# loc_board1.net
KiCad netlist of a schematic drawn in EAGLE
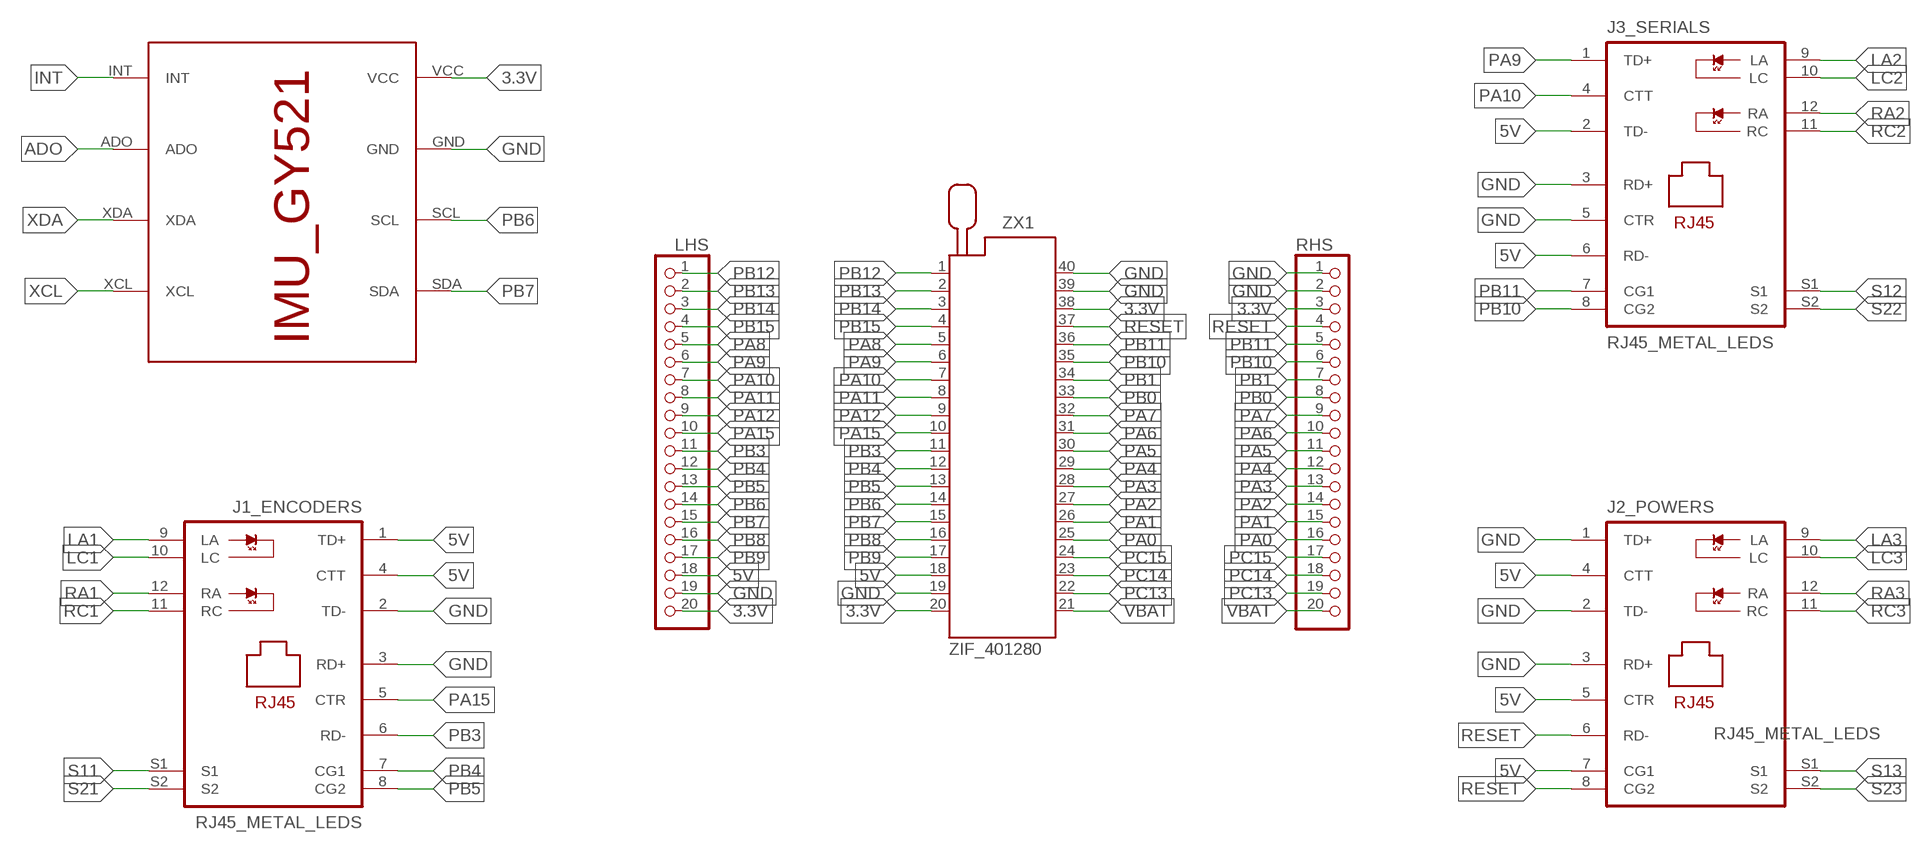
[diagram p0: schematic, sheet 1]

(export (version "E")
  (design (tool "Eeschema 10.0.6"))
  (components
    (comp (ref "IMU_")
      (value "IMU_ROBOCON_GY521")
      (footprint "eagle-import:IMU_GY521")
      (libsource (lib "eagle-import") (part "IMU_ROBOCON_GY521"))
    )
    (comp (ref "J1_ENCODERS")
      (value "RJ45_METAL_LEDS")
      (footprint "eagle-import:J0-A_B_F")
      (libsource (lib "eagle-import") (part "RJ45_METAL_LEDS"))
    )
    (comp (ref "J2_POWERS")
      (value "RJ45_METAL_LEDS")
      (footprint "eagle-import:J0-A_B_F")
      (libsource (lib "eagle-import") (part "RJ45_METAL_LEDS"))
    )
    (comp (ref "J3_SERIALS")
      (value "RJ45_METAL_LEDS")
      (footprint "eagle-import:J0-A_B_F")
      (libsource (lib "eagle-import") (part "RJ45_METAL_LEDS"))
    )
    (comp (ref "LHS")
      (value "PINHD-1X20")
      (footprint "eagle-import:1X20")
      (libsource (lib "eagle-import") (part "PINHD-1X20"))
    )
    (comp (ref "RHS")
      (value "PINHD-1X20")
      (footprint "eagle-import:1X20")
      (libsource (lib "eagle-import") (part "PINHD-1X20"))
    )
    (comp (ref "ZX1")
      (value "ZIF_401280")
      (footprint "eagle-import:240-1280-00-0602J")
      (libsource (lib "eagle-import") (part "ZIF_401280"))
    )
  )
  (nets
    (net (code "1") (name "3.3V") (class "Default")
      (node (ref "IMU_") (pin "VCC") (pinfunction "VCC_VCC") (pintype "bidirectional"))
      (node (ref "LHS") (pin "20") (pinfunction "20_20") (pintype "passive"))
      (node (ref "RHS") (pin "3") (pinfunction "3_3") (pintype "passive"))
      (node (ref "ZX1") (pin "20") (pinfunction "20_20") (pintype "passive"))
      (node (ref "ZX1") (pin "38") (pinfunction "38_38") (pintype "passive"))
    )
    (net (code "2") (name "5V") (class "Default")
      (node (ref "J1_ENCODERS") (pin "1") (pinfunction "TD+_1") (pintype "passive"))
      (node (ref "J1_ENCODERS") (pin "4") (pinfunction "CTT_4") (pintype "passive"))
      (node (ref "J2_POWERS") (pin "4") (pinfunction "CTT_4") (pintype "passive"))
      (node (ref "J2_POWERS") (pin "5") (pinfunction "CTR_5") (pintype "passive"))
      (node (ref "J2_POWERS") (pin "7") (pinfunction "CG1_7") (pintype "passive"))
      (node (ref "J3_SERIALS") (pin "2") (pinfunction "TD-_2") (pintype "passive"))
      (node (ref "J3_SERIALS") (pin "6") (pinfunction "RD-_6") (pintype "passive"))
      (node (ref "LHS") (pin "18") (pinfunction "18_18") (pintype "passive"))
      (node (ref "ZX1") (pin "18") (pinfunction "18_18") (pintype "passive"))
    )
    (net (code "3") (name "ADO") (class "Default")
      (node (ref "IMU_") (pin "ADO") (pinfunction "ADO_ADO") (pintype "bidirectional"))
    )
    (net (code "4") (name "GND") (class "Default")
      (node (ref "IMU_") (pin "GND") (pinfunction "GND_GND") (pintype "bidirectional"))
      (node (ref "J1_ENCODERS") (pin "2") (pinfunction "TD-_2") (pintype "passive"))
      (node (ref "J1_ENCODERS") (pin "3") (pinfunction "RD+_3") (pintype "passive"))
      (node (ref "J2_POWERS") (pin "1") (pinfunction "TD+_1") (pintype "passive"))
      (node (ref "J2_POWERS") (pin "2") (pinfunction "TD-_2") (pintype "passive"))
      (node (ref "J2_POWERS") (pin "3") (pinfunction "RD+_3") (pintype "passive"))
      (node (ref "J3_SERIALS") (pin "3") (pinfunction "RD+_3") (pintype "passive"))
      (node (ref "J3_SERIALS") (pin "5") (pinfunction "CTR_5") (pintype "passive"))
      (node (ref "LHS") (pin "19") (pinfunction "19_19") (pintype "passive"))
      (node (ref "RHS") (pin "1") (pinfunction "1_1") (pintype "passive"))
      (node (ref "RHS") (pin "2") (pinfunction "2_2") (pintype "passive"))
      (node (ref "ZX1") (pin "19") (pinfunction "19_19") (pintype "passive"))
      (node (ref "ZX1") (pin "39") (pinfunction "39_39") (pintype "passive"))
      (node (ref "ZX1") (pin "40") (pinfunction "40_40") (pintype "passive"))
    )
    (net (code "5") (name "INT") (class "Default")
      (node (ref "IMU_") (pin "INT") (pinfunction "INT_INT") (pintype "bidirectional"))
    )
    (net (code "6") (name "LA1") (class "Default")
      (node (ref "J1_ENCODERS") (pin "9") (pinfunction "LA_9") (pintype "passive"))
    )
    (net (code "7") (name "LA2") (class "Default")
      (node (ref "J3_SERIALS") (pin "9") (pinfunction "LA_9") (pintype "passive"))
    )
    (net (code "8") (name "LA3") (class "Default")
      (node (ref "J2_POWERS") (pin "9") (pinfunction "LA_9") (pintype "passive"))
    )
    (net (code "9") (name "LC1") (class "Default")
      (node (ref "J1_ENCODERS") (pin "10") (pinfunction "LC_10") (pintype "passive"))
    )
    (net (code "10") (name "LC2") (class "Default")
      (node (ref "J3_SERIALS") (pin "10") (pinfunction "LC_10") (pintype "passive"))
    )
    (net (code "11") (name "LC3") (class "Default")
      (node (ref "J2_POWERS") (pin "10") (pinfunction "LC_10") (pintype "passive"))
    )
    (net (code "12") (name "PA0") (class "Default")
      (node (ref "RHS") (pin "16") (pinfunction "16_16") (pintype "passive"))
      (node (ref "ZX1") (pin "25") (pinfunction "25_25") (pintype "passive"))
    )
    (net (code "13") (name "PA1") (class "Default")
      (node (ref "RHS") (pin "15") (pinfunction "15_15") (pintype "passive"))
      (node (ref "ZX1") (pin "26") (pinfunction "26_26") (pintype "passive"))
    )
    (net (code "14") (name "PA2") (class "Default")
      (node (ref "RHS") (pin "14") (pinfunction "14_14") (pintype "passive"))
      (node (ref "ZX1") (pin "27") (pinfunction "27_27") (pintype "passive"))
    )
    (net (code "15") (name "PA3") (class "Default")
      (node (ref "RHS") (pin "13") (pinfunction "13_13") (pintype "passive"))
      (node (ref "ZX1") (pin "28") (pinfunction "28_28") (pintype "passive"))
    )
    (net (code "16") (name "PA4") (class "Default")
      (node (ref "RHS") (pin "12") (pinfunction "12_12") (pintype "passive"))
      (node (ref "ZX1") (pin "29") (pinfunction "29_29") (pintype "passive"))
    )
    (net (code "17") (name "PA5") (class "Default")
      (node (ref "RHS") (pin "11") (pinfunction "11_11") (pintype "passive"))
      (node (ref "ZX1") (pin "30") (pinfunction "30_30") (pintype "passive"))
    )
    (net (code "18") (name "PA6") (class "Default")
      (node (ref "RHS") (pin "10") (pinfunction "10_10") (pintype "passive"))
      (node (ref "ZX1") (pin "31") (pinfunction "31_31") (pintype "passive"))
    )
    (net (code "19") (name "PA7") (class "Default")
      (node (ref "RHS") (pin "9") (pinfunction "9_9") (pintype "passive"))
      (node (ref "ZX1") (pin "32") (pinfunction "32_32") (pintype "passive"))
    )
    (net (code "20") (name "PA8") (class "Default")
      (node (ref "LHS") (pin "5") (pinfunction "5_5") (pintype "passive"))
      (node (ref "ZX1") (pin "5") (pinfunction "5_5") (pintype "passive"))
    )
    (net (code "21") (name "PA9") (class "Default")
      (node (ref "J3_SERIALS") (pin "1") (pinfunction "TD+_1") (pintype "passive"))
      (node (ref "LHS") (pin "6") (pinfunction "6_6") (pintype "passive"))
      (node (ref "ZX1") (pin "6") (pinfunction "6_6") (pintype "passive"))
    )
    (net (code "22") (name "PA10") (class "Default")
      (node (ref "J3_SERIALS") (pin "4") (pinfunction "CTT_4") (pintype "passive"))
      (node (ref "LHS") (pin "7") (pinfunction "7_7") (pintype "passive"))
      (node (ref "ZX1") (pin "7") (pinfunction "7_7") (pintype "passive"))
    )
    (net (code "23") (name "PA11") (class "Default")
      (node (ref "LHS") (pin "8") (pinfunction "8_8") (pintype "passive"))
      (node (ref "ZX1") (pin "8") (pinfunction "8_8") (pintype "passive"))
    )
    (net (code "24") (name "PA12") (class "Default")
      (node (ref "LHS") (pin "9") (pinfunction "9_9") (pintype "passive"))
      (node (ref "ZX1") (pin "9") (pinfunction "9_9") (pintype "passive"))
    )
    (net (code "25") (name "PA15") (class "Default")
      (node (ref "J1_ENCODERS") (pin "5") (pinfunction "CTR_5") (pintype "passive"))
      (node (ref "LHS") (pin "10") (pinfunction "10_10") (pintype "passive"))
      (node (ref "ZX1") (pin "10") (pinfunction "10_10") (pintype "passive"))
    )
    (net (code "26") (name "PB0") (class "Default")
      (node (ref "RHS") (pin "8") (pinfunction "8_8") (pintype "passive"))
      (node (ref "ZX1") (pin "33") (pinfunction "33_33") (pintype "passive"))
    )
    (net (code "27") (name "PB1") (class "Default")
      (node (ref "RHS") (pin "7") (pinfunction "7_7") (pintype "passive"))
      (node (ref "ZX1") (pin "34") (pinfunction "34_34") (pintype "passive"))
    )
    (net (code "28") (name "PB3") (class "Default")
      (node (ref "J1_ENCODERS") (pin "6") (pinfunction "RD-_6") (pintype "passive"))
      (node (ref "LHS") (pin "11") (pinfunction "11_11") (pintype "passive"))
      (node (ref "ZX1") (pin "11") (pinfunction "11_11") (pintype "passive"))
    )
    (net (code "29") (name "PB4") (class "Default")
      (node (ref "J1_ENCODERS") (pin "7") (pinfunction "CG1_7") (pintype "passive"))
      (node (ref "LHS") (pin "12") (pinfunction "12_12") (pintype "passive"))
      (node (ref "ZX1") (pin "12") (pinfunction "12_12") (pintype "passive"))
    )
    (net (code "30") (name "PB5") (class "Default")
      (node (ref "J1_ENCODERS") (pin "8") (pinfunction "CG2_8") (pintype "passive"))
      (node (ref "LHS") (pin "13") (pinfunction "13_13") (pintype "passive"))
      (node (ref "ZX1") (pin "13") (pinfunction "13_13") (pintype "passive"))
    )
    (net (code "31") (name "PB6") (class "Default")
      (node (ref "IMU_") (pin "SCL") (pinfunction "SCL_SCL") (pintype "bidirectional"))
      (node (ref "LHS") (pin "14") (pinfunction "14_14") (pintype "passive"))
      (node (ref "ZX1") (pin "14") (pinfunction "14_14") (pintype "passive"))
    )
    (net (code "32") (name "PB7") (class "Default")
      (node (ref "IMU_") (pin "SDA") (pinfunction "SDA_SDA") (pintype "bidirectional"))
      (node (ref "LHS") (pin "15") (pinfunction "15_15") (pintype "passive"))
      (node (ref "ZX1") (pin "15") (pinfunction "15_15") (pintype "passive"))
    )
    (net (code "33") (name "PB8") (class "Default")
      (node (ref "LHS") (pin "16") (pinfunction "16_16") (pintype "passive"))
      (node (ref "ZX1") (pin "16") (pinfunction "16_16") (pintype "passive"))
    )
    (net (code "34") (name "PB9") (class "Default")
      (node (ref "LHS") (pin "17") (pinfunction "17_17") (pintype "passive"))
      (node (ref "ZX1") (pin "17") (pinfunction "17_17") (pintype "passive"))
    )
    (net (code "35") (name "PB10") (class "Default")
      (node (ref "J3_SERIALS") (pin "8") (pinfunction "CG2_8") (pintype "passive"))
      (node (ref "RHS") (pin "6") (pinfunction "6_6") (pintype "passive"))
      (node (ref "ZX1") (pin "35") (pinfunction "35_35") (pintype "passive"))
    )
    (net (code "36") (name "PB11") (class "Default")
      (node (ref "J3_SERIALS") (pin "7") (pinfunction "CG1_7") (pintype "passive"))
      (node (ref "RHS") (pin "5") (pinfunction "5_5") (pintype "passive"))
      (node (ref "ZX1") (pin "36") (pinfunction "36_36") (pintype "passive"))
    )
    (net (code "37") (name "PB12") (class "Default")
      (node (ref "LHS") (pin "1") (pinfunction "1_1") (pintype "passive"))
      (node (ref "ZX1") (pin "1") (pinfunction "1_1") (pintype "passive"))
    )
    (net (code "38") (name "PB13") (class "Default")
      (node (ref "LHS") (pin "2") (pinfunction "2_2") (pintype "passive"))
      (node (ref "ZX1") (pin "2") (pinfunction "2_2") (pintype "passive"))
    )
    (net (code "39") (name "PB14") (class "Default")
      (node (ref "LHS") (pin "3") (pinfunction "3_3") (pintype "passive"))
      (node (ref "ZX1") (pin "3") (pinfunction "3_3") (pintype "passive"))
    )
    (net (code "40") (name "PB15") (class "Default")
      (node (ref "LHS") (pin "4") (pinfunction "4_4") (pintype "passive"))
      (node (ref "ZX1") (pin "4") (pinfunction "4_4") (pintype "passive"))
    )
    (net (code "41") (name "PC13") (class "Default")
      (node (ref "RHS") (pin "19") (pinfunction "19_19") (pintype "passive"))
      (node (ref "ZX1") (pin "22") (pinfunction "22_22") (pintype "passive"))
    )
    (net (code "42") (name "PC14") (class "Default")
      (node (ref "RHS") (pin "18") (pinfunction "18_18") (pintype "passive"))
      (node (ref "ZX1") (pin "23") (pinfunction "23_23") (pintype "passive"))
    )
    (net (code "43") (name "PC15") (class "Default")
      (node (ref "RHS") (pin "17") (pinfunction "17_17") (pintype "passive"))
      (node (ref "ZX1") (pin "24") (pinfunction "24_24") (pintype "passive"))
    )
    (net (code "44") (name "RA1") (class "Default")
      (node (ref "J1_ENCODERS") (pin "12") (pinfunction "RA_12") (pintype "passive"))
    )
    (net (code "45") (name "RA2") (class "Default")
      (node (ref "J3_SERIALS") (pin "12") (pinfunction "RA_12") (pintype "passive"))
    )
    (net (code "46") (name "RA3") (class "Default")
      (node (ref "J2_POWERS") (pin "12") (pinfunction "RA_12") (pintype "passive"))
    )
    (net (code "47") (name "RC1") (class "Default")
      (node (ref "J1_ENCODERS") (pin "11") (pinfunction "RC_11") (pintype "passive"))
    )
    (net (code "48") (name "RC2") (class "Default")
      (node (ref "J3_SERIALS") (pin "11") (pinfunction "RC_11") (pintype "passive"))
    )
    (net (code "49") (name "RC3") (class "Default")
      (node (ref "J2_POWERS") (pin "11") (pinfunction "RC_11") (pintype "passive"))
    )
    (net (code "50") (name "RESET") (class "Default")
      (node (ref "J2_POWERS") (pin "6") (pinfunction "RD-_6") (pintype "passive"))
      (node (ref "J2_POWERS") (pin "8") (pinfunction "CG2_8") (pintype "passive"))
      (node (ref "RHS") (pin "4") (pinfunction "4_4") (pintype "passive"))
      (node (ref "ZX1") (pin "37") (pinfunction "37_37") (pintype "passive"))
    )
    (net (code "51") (name "S11") (class "Default")
      (node (ref "J1_ENCODERS") (pin "S1") (pinfunction "S1_S1") (pintype "passive"))
    )
    (net (code "52") (name "S12") (class "Default")
      (node (ref "J3_SERIALS") (pin "S1") (pinfunction "S1_S1") (pintype "passive"))
    )
    (net (code "53") (name "S13") (class "Default")
      (node (ref "J2_POWERS") (pin "S1") (pinfunction "S1_S1") (pintype "passive"))
    )
    (net (code "54") (name "S21") (class "Default")
      (node (ref "J1_ENCODERS") (pin "S2") (pinfunction "S2_S2") (pintype "passive"))
    )
    (net (code "55") (name "S22") (class "Default")
      (node (ref "J3_SERIALS") (pin "S2") (pinfunction "S2_S2") (pintype "passive"))
    )
    (net (code "56") (name "S23") (class "Default")
      (node (ref "J2_POWERS") (pin "S2") (pinfunction "S2_S2") (pintype "passive"))
    )
    (net (code "57") (name "VBAT") (class "Default")
      (node (ref "RHS") (pin "20") (pinfunction "20_20") (pintype "passive"))
      (node (ref "ZX1") (pin "21") (pinfunction "21_21") (pintype "passive"))
    )
    (net (code "58") (name "XCL") (class "Default")
      (node (ref "IMU_") (pin "XCL") (pinfunction "XCL_XCL") (pintype "bidirectional"))
    )
    (net (code "59") (name "XDA") (class "Default")
      (node (ref "IMU_") (pin "XDA") (pinfunction "XDA_XDA") (pintype "bidirectional"))
    )
  )
)
